# 1_mb_conn.net
KiCad netlist of a schematic drawn in Altium Designer
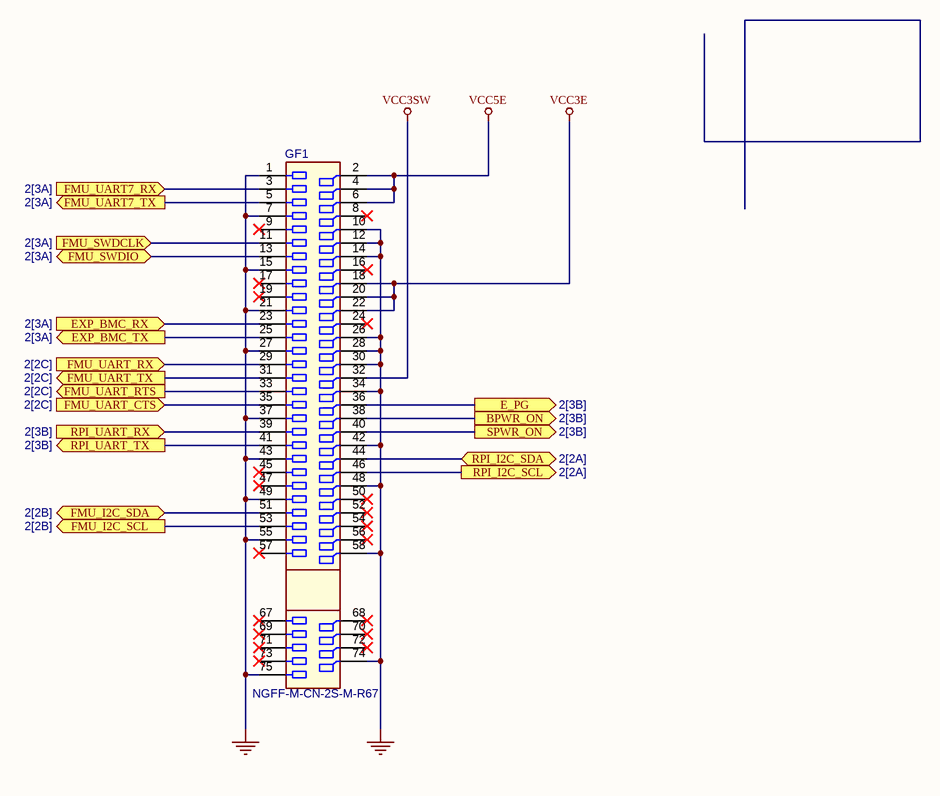
[diagram p0: 1_mb_conn.SchDoc]

(export (version "E")
  (design (tool "Eeschema 10.0.6"))
  (components
    (comp (ref "GF1")
      (value "NGFF-M-CN-2S-M-R67")
      (footprint "NGFF-M-GF-2D-500-1K-S67")
      (description "Golden finger, NGFF key M, Dual, Staggered, Pitch 0.5mm, 67-Position")
      (libsource (lib "<Company> Server") (part "CMP-00506-3"))
    )
  )
  (nets
    (net (code "1") (name "/BPWR_ON") (class "Default")
      (node (ref "GF1") (pin "38") (pinfunction "38_38") (pintype "passive"))
    )
    (net (code "2") (name "/EXP_BMC_RX") (class "Default")
      (node (ref "GF1") (pin "23") (pinfunction "23_23") (pintype "passive"))
    )
    (net (code "3") (name "/EXP_BMC_TX") (class "Default")
      (node (ref "GF1") (pin "25") (pinfunction "25_25") (pintype "passive"))
    )
    (net (code "4") (name "/E_PG") (class "Default")
      (node (ref "GF1") (pin "36") (pinfunction "36_36") (pintype "passive"))
    )
    (net (code "5") (name "/FMU_I2C_SCL") (class "Default")
      (node (ref "GF1") (pin "53") (pinfunction "53_53") (pintype "passive"))
    )
    (net (code "6") (name "/FMU_I2C_SDA") (class "Default")
      (node (ref "GF1") (pin "51") (pinfunction "51_51") (pintype "passive"))
    )
    (net (code "7") (name "/FMU_SWDCLK") (class "Default")
      (node (ref "GF1") (pin "11") (pinfunction "11_11") (pintype "passive"))
    )
    (net (code "8") (name "/FMU_SWDIO") (class "Default")
      (node (ref "GF1") (pin "13") (pinfunction "13_13") (pintype "passive"))
    )
    (net (code "9") (name "/FMU_UART7_RX") (class "Default")
      (node (ref "GF1") (pin "3") (pinfunction "3_3") (pintype "passive"))
    )
    (net (code "10") (name "/FMU_UART7_TX") (class "Default")
      (node (ref "GF1") (pin "5") (pinfunction "5_5") (pintype "passive"))
    )
    (net (code "11") (name "/FMU_UART_CTS") (class "Default")
      (node (ref "GF1") (pin "35") (pinfunction "35_35") (pintype "passive"))
    )
    (net (code "12") (name "/FMU_UART_RTS") (class "Default")
      (node (ref "GF1") (pin "33") (pinfunction "33_33") (pintype "passive"))
    )
    (net (code "13") (name "/FMU_UART_RX") (class "Default")
      (node (ref "GF1") (pin "29") (pinfunction "29_29") (pintype "passive"))
    )
    (net (code "14") (name "/FMU_UART_TX") (class "Default")
      (node (ref "GF1") (pin "31") (pinfunction "31_31") (pintype "passive"))
    )
    (net (code "15") (name "/RPI_I2C_SCL") (class "Default")
      (node (ref "GF1") (pin "46") (pinfunction "46_46") (pintype "passive"))
    )
    (net (code "16") (name "/RPI_I2C_SDA") (class "Default")
      (node (ref "GF1") (pin "44") (pinfunction "44_44") (pintype "passive"))
    )
    (net (code "17") (name "/RPI_UART_RX") (class "Default")
      (node (ref "GF1") (pin "39") (pinfunction "39_39") (pintype "passive"))
    )
    (net (code "18") (name "/RPI_UART_TX") (class "Default")
      (node (ref "GF1") (pin "41") (pinfunction "41_41") (pintype "passive"))
    )
    (net (code "19") (name "/SPWR_ON") (class "Default")
      (node (ref "GF1") (pin "40") (pinfunction "40_40") (pintype "passive"))
    )
    (net (code "20") (name "GND") (class "Default")
      (node (ref "GF1") (pin "1") (pinfunction "1_1") (pintype "passive"))
      (node (ref "GF1") (pin "10") (pinfunction "10_10") (pintype "passive"))
      (node (ref "GF1") (pin "12") (pinfunction "12_12") (pintype "passive"))
      (node (ref "GF1") (pin "14") (pinfunction "14_14") (pintype "passive"))
      (node (ref "GF1") (pin "15") (pinfunction "15_15") (pintype "passive"))
      (node (ref "GF1") (pin "21") (pinfunction "21_21") (pintype "passive"))
      (node (ref "GF1") (pin "26") (pinfunction "26_26") (pintype "passive"))
      (node (ref "GF1") (pin "27") (pinfunction "27_27") (pintype "passive"))
      (node (ref "GF1") (pin "28") (pinfunction "28_28") (pintype "passive"))
      (node (ref "GF1") (pin "30") (pinfunction "30_30") (pintype "passive"))
      (node (ref "GF1") (pin "34") (pinfunction "34_34") (pintype "passive"))
      (node (ref "GF1") (pin "37") (pinfunction "37_37") (pintype "passive"))
      (node (ref "GF1") (pin "42") (pinfunction "42_42") (pintype "passive"))
      (node (ref "GF1") (pin "43") (pinfunction "43_43") (pintype "passive"))
      (node (ref "GF1") (pin "48") (pinfunction "48_48") (pintype "passive"))
      (node (ref "GF1") (pin "49") (pinfunction "49_49") (pintype "passive"))
      (node (ref "GF1") (pin "55") (pinfunction "55_55") (pintype "passive"))
      (node (ref "GF1") (pin "58") (pinfunction "58_58") (pintype "passive"))
      (node (ref "GF1") (pin "7") (pinfunction "7_7") (pintype "passive"))
      (node (ref "GF1") (pin "74") (pinfunction "74_74") (pintype "passive"))
      (node (ref "GF1") (pin "75") (pinfunction "75_75") (pintype "passive"))
    )
    (net (code "21") (name "VCC3E") (class "Default")
      (node (ref "GF1") (pin "18") (pinfunction "18_18") (pintype "passive"))
      (node (ref "GF1") (pin "20") (pinfunction "20_20") (pintype "passive"))
      (node (ref "GF1") (pin "22") (pinfunction "22_22") (pintype "passive"))
    )
    (net (code "22") (name "VCC3SW") (class "Default")
      (node (ref "GF1") (pin "32") (pinfunction "32_32") (pintype "passive"))
    )
    (net (code "23") (name "VCC5E") (class "Default")
      (node (ref "GF1") (pin "2") (pinfunction "2_2") (pintype "passive"))
      (node (ref "GF1") (pin "4") (pinfunction "4_4") (pintype "passive"))
      (node (ref "GF1") (pin "6") (pinfunction "6_6") (pintype "passive"))
    )
    (net (code "24") (name "unconnected-(GF1-Pad8)") (class "Default")
      (node (ref "GF1") (pin "8") (pinfunction "8_8") (pintype "passive+no_connect"))
    )
    (net (code "25") (name "unconnected-(GF1-Pad9)") (class "Default")
      (node (ref "GF1") (pin "9") (pinfunction "9_9") (pintype "passive+no_connect"))
    )
    (net (code "26") (name "unconnected-(GF1-Pad16)") (class "Default")
      (node (ref "GF1") (pin "16") (pinfunction "16_16") (pintype "passive+no_connect"))
    )
    (net (code "27") (name "unconnected-(GF1-Pad17)") (class "Default")
      (node (ref "GF1") (pin "17") (pinfunction "17_17") (pintype "passive+no_connect"))
    )
    (net (code "28") (name "unconnected-(GF1-Pad19)") (class "Default")
      (node (ref "GF1") (pin "19") (pinfunction "19_19") (pintype "passive+no_connect"))
    )
    (net (code "29") (name "unconnected-(GF1-Pad24)") (class "Default")
      (node (ref "GF1") (pin "24") (pinfunction "24_24") (pintype "passive+no_connect"))
    )
    (net (code "30") (name "unconnected-(GF1-Pad45)") (class "Default")
      (node (ref "GF1") (pin "45") (pinfunction "45_45") (pintype "passive+no_connect"))
    )
    (net (code "31") (name "unconnected-(GF1-Pad47)") (class "Default")
      (node (ref "GF1") (pin "47") (pinfunction "47_47") (pintype "passive+no_connect"))
    )
    (net (code "32") (name "unconnected-(GF1-Pad50)") (class "Default")
      (node (ref "GF1") (pin "50") (pinfunction "50_50") (pintype "passive+no_connect"))
    )
    (net (code "33") (name "unconnected-(GF1-Pad52)") (class "Default")
      (node (ref "GF1") (pin "52") (pinfunction "52_52") (pintype "passive+no_connect"))
    )
    (net (code "34") (name "unconnected-(GF1-Pad54)") (class "Default")
      (node (ref "GF1") (pin "54") (pinfunction "54_54") (pintype "passive+no_connect"))
    )
    (net (code "35") (name "unconnected-(GF1-Pad56)") (class "Default")
      (node (ref "GF1") (pin "56") (pinfunction "56_56") (pintype "passive+no_connect"))
    )
    (net (code "36") (name "unconnected-(GF1-Pad57)") (class "Default")
      (node (ref "GF1") (pin "57") (pinfunction "57_57") (pintype "passive+no_connect"))
    )
    (net (code "37") (name "unconnected-(GF1-Pad67)") (class "Default")
      (node (ref "GF1") (pin "67") (pinfunction "67_67") (pintype "passive+no_connect"))
    )
    (net (code "38") (name "unconnected-(GF1-Pad68)") (class "Default")
      (node (ref "GF1") (pin "68") (pinfunction "68_68") (pintype "passive+no_connect"))
    )
    (net (code "39") (name "unconnected-(GF1-Pad69)") (class "Default")
      (node (ref "GF1") (pin "69") (pinfunction "69_69") (pintype "passive+no_connect"))
    )
    (net (code "40") (name "unconnected-(GF1-Pad70)") (class "Default")
      (node (ref "GF1") (pin "70") (pinfunction "70_70") (pintype "passive+no_connect"))
    )
    (net (code "41") (name "unconnected-(GF1-Pad71)") (class "Default")
      (node (ref "GF1") (pin "71") (pinfunction "71_71") (pintype "passive+no_connect"))
    )
    (net (code "42") (name "unconnected-(GF1-Pad72)") (class "Default")
      (node (ref "GF1") (pin "72") (pinfunction "72_72") (pintype "passive+no_connect"))
    )
    (net (code "43") (name "unconnected-(GF1-Pad73)") (class "Default")
      (node (ref "GF1") (pin "73") (pinfunction "73_73") (pintype "passive+no_connect"))
    )
  )
)
